# calculator.net
KiCad netlist of a schematic drawn in Altium Designer
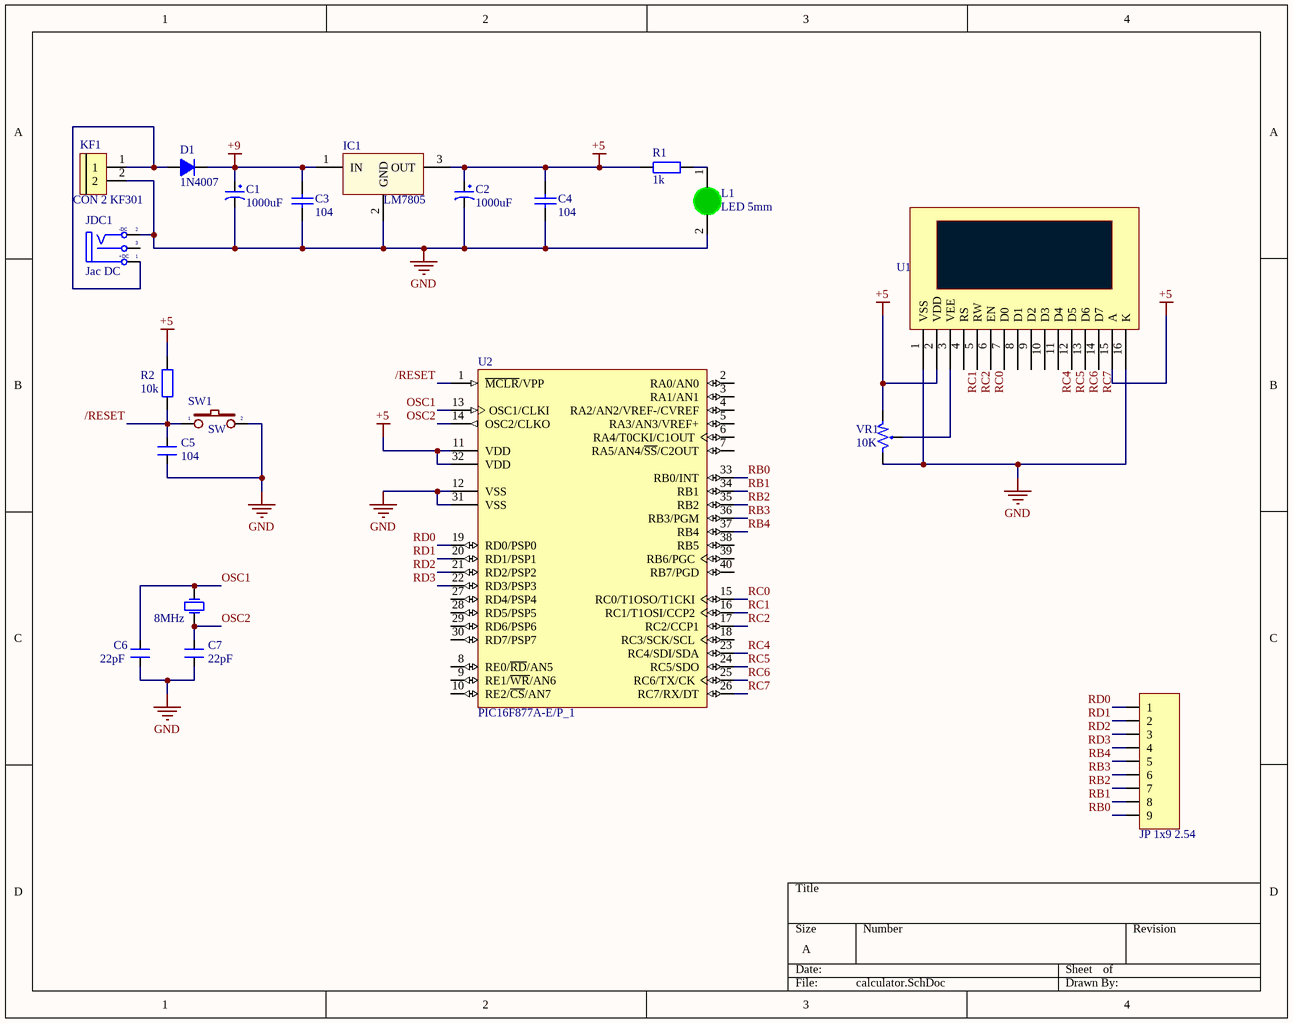
[diagram p0: calculator.SchDoc]

(export (version "E")
  (design (tool "Eeschema 10.0.6"))
  (components
    (comp (ref "C1")
      (value "1000uF")
      (footprint "tu hoa 8mm")
      (description "Cắm")
      (libsource (lib "Capacitor") (part "Tu Hoa 1000uF 16V 8x20"))
    )
    (comp (ref "C2")
      (value "1000uF")
      (footprint "tu hoa 8mm")
      (description "Cắm")
      (libsource (lib "Capacitor") (part "Tu Hoa 1000uF 16V 8x20"))
    )
    (comp (ref "C3")
      (value "104")
      (footprint "tu gom")
      (description "Cắm")
      (libsource (lib "Capacitor") (part "Tu gom 104 50V"))
    )
    (comp (ref "C4")
      (value "104")
      (footprint "tu gom")
      (description "Cắm")
      (libsource (lib "Capacitor") (part "Tu gom 104 50V"))
    )
    (comp (ref "C5")
      (value "104")
      (footprint "CN1.5")
      (description "Cap np 682pF => 104pF")
      (libsource (lib "Cty1") (part "CN1.5"))
    )
    (comp (ref "C6")
      (value "22pF")
      (footprint "CN1.5")
      (description "Cap np 682pF => 104pF")
      (libsource (lib "Cty1") (part "CN1.5"))
    )
    (comp (ref "C7")
      (value "22pF")
      (footprint "CN1.5")
      (description "Cap np 682pF => 104pF")
      (libsource (lib "Cty1") (part "CN1.5"))
    )
    (comp (ref "D1")
      (value "1N4007")
      (footprint "D1A")
      (description "Diode 1A")
      (libsource (lib "Cty1") (part "D1A"))
    )
    (comp (ref "IC1")
      (value "LM7805")
      (footprint "QTO-220")
      (description "On ap +, from + 5 to + 24VDC")
      (libsource (lib "Cty1") (part "LM78xx"))
    )
    (comp (ref "JDC1")
      (value "Jac DC")
      (footprint "DC-IN")
      (description "Jac DC input")
      (libsource (lib "Cty1") (part "DCIN"))
    )
    (comp (ref "JP1")
      (value "JP 1x9 2.54")
      (footprint "JP 1x9 DT")
      (description "Cắm")
      (libsource (lib "Jump") (part "JP 1x9 2.54 Duc Thang"))
    )
    (comp (ref "KF1")
      (value "CON 2 KF301")
      (footprint "Con 2 KF301 5.08")
      (description "Cắm")
      (libsource (lib "Connector") (part "CON 2 KF301"))
    )
    (comp (ref "L1")
      (value "LED 5mm")
      (footprint "LED-5MM-Green")
      (description "Cắm")
      (libsource (lib "Led") (part "LED 5mm Xanh La"))
    )
    (comp (ref "R1")
      (value "1k")
      (footprint "tro vach 1/4w")
      (description "Cắm")
      (libsource (lib "Resistor") (part "Tro Vach 1/4W 5% 1k"))
    )
    (comp (ref "R2")
      (value "10k")
      (footprint "R1/4W")
      (description "Resistor 1/4W")
      (libsource (lib "Cty1") (part "R1/4W"))
    )
    (comp (ref "SW1")
      (value "SW")
      (footprint "SW2")
      (description "Switch button 2 pin")
      (libsource (lib "Cty1") (part "SW2"))
    )
    (comp (ref "U1") (value "LCD") (footprint "LCD16X2") (libsource (lib "Cty1") (part "LCD")))
    (comp (ref "U2")
      (value "PIC16F877A-E/P_1")
      (footprint "PDIP600-P40")
      (fields (field (name "PUBLISHER") "Altium Limited"))
      (libsource (lib "Cty1") (part "PIC16F877A-E/P_1"))
    )
    (comp (ref "VR1")
      (value "10K")
      (footprint "VR1")
      (description "Var Resistor")
      (libsource (lib "syhaunguyen") (part "VR1"))
    )
    (comp (ref "Y1")
      (value "8MHz")
      (footprint "XT2")
      (description "Crystal Oscillator")
      (fields (field (name "PUBLISHER") "Altium Limited"))
      (libsource (lib "Cty1") (part "Crystal"))
    )
  )
  (nets
    (net (code "1") (name "+5") (class "Default")
      (node (ref "C2") (pin "1") (pinfunction "1_1") (pintype "passive"))
      (node (ref "C4") (pin "1") (pinfunction "1_1") (pintype "passive"))
      (node (ref "IC1") (pin "3") (pinfunction "OUT_3") (pintype "passive"))
      (node (ref "R1") (pin "2") (pinfunction "2_2") (pintype "passive"))
      (node (ref "R2") (pin "2") (pinfunction "2_2") (pintype "passive"))
      (node (ref "U1") (pin "15") (pinfunction "A_15") (pintype "passive"))
      (node (ref "U1") (pin "2") (pinfunction "VDD_2") (pintype "passive"))
      (node (ref "U2") (pin "11") (pinfunction "VDD_11") (pintype "power_in"))
      (node (ref "U2") (pin "32") (pinfunction "VDD_32") (pintype "power_in"))
      (node (ref "VR1") (pin "1") (pinfunction "1_1") (pintype "passive"))
    )
    (net (code "2") (name "+9") (class "Default")
      (node (ref "C1") (pin "1") (pinfunction "1_1") (pintype "passive"))
      (node (ref "C3") (pin "1") (pinfunction "1_1") (pintype "passive"))
      (node (ref "D1") (pin "2") (pinfunction "K_2") (pintype "passive"))
      (node (ref "IC1") (pin "1") (pinfunction "IN_1") (pintype "passive"))
    )
    (net (code "3") (name "/OSC1") (class "Default")
      (node (ref "C6") (pin "2") (pinfunction "2_2") (pintype "passive"))
      (node (ref "U2") (pin "13") (pinfunction "OSC1/CLKI_13") (pintype "input"))
      (node (ref "Y1") (pin "1") (pinfunction "OSC1_1") (pintype "passive"))
    )
    (net (code "4") (name "/OSC2") (class "Default")
      (node (ref "C7") (pin "2") (pinfunction "2_2") (pintype "passive"))
      (node (ref "U2") (pin "14") (pinfunction "OSC2/CLKO_14") (pintype "output"))
      (node (ref "Y1") (pin "2") (pinfunction "OSC2_2") (pintype "passive"))
    )
    (net (code "5") (name "/RB0") (class "Default")
      (node (ref "JP1") (pin "9") (pinfunction "9_9") (pintype "passive"))
      (node (ref "U2") (pin "33") (pinfunction "RB0/INT_33") (pintype "bidirectional"))
    )
    (net (code "6") (name "/RB1") (class "Default")
      (node (ref "JP1") (pin "8") (pinfunction "8_8") (pintype "passive"))
      (node (ref "U2") (pin "34") (pinfunction "RB1_34") (pintype "bidirectional"))
    )
    (net (code "7") (name "/RB2") (class "Default")
      (node (ref "JP1") (pin "7") (pinfunction "7_7") (pintype "passive"))
      (node (ref "U2") (pin "35") (pinfunction "RB2_35") (pintype "bidirectional"))
    )
    (net (code "8") (name "/RB3") (class "Default")
      (node (ref "JP1") (pin "6") (pinfunction "6_6") (pintype "passive"))
      (node (ref "U2") (pin "36") (pinfunction "RB3/PGM_36") (pintype "bidirectional"))
    )
    (net (code "9") (name "/RB4") (class "Default")
      (node (ref "JP1") (pin "5") (pinfunction "5_5") (pintype "passive"))
      (node (ref "U2") (pin "37") (pinfunction "RB4_37") (pintype "bidirectional"))
    )
    (net (code "10") (name "/RC0") (class "Default")
      (node (ref "U1") (pin "6") (pinfunction "EN_6") (pintype "passive"))
      (node (ref "U2") (pin "15") (pinfunction "RC0/T1OSO/T1CKI_15") (pintype "bidirectional"))
    )
    (net (code "11") (name "/RC1") (class "Default")
      (node (ref "U1") (pin "4") (pinfunction "RS_4") (pintype "passive"))
      (node (ref "U2") (pin "16") (pinfunction "RC1/T1OSI/CCP2_16") (pintype "bidirectional"))
    )
    (net (code "12") (name "/RC2") (class "Default")
      (node (ref "U1") (pin "5") (pinfunction "RW_5") (pintype "passive"))
      (node (ref "U2") (pin "17") (pinfunction "RC2/CCP1_17") (pintype "bidirectional"))
    )
    (net (code "13") (name "/RC4") (class "Default")
      (node (ref "U1") (pin "11") (pinfunction "D4_11") (pintype "passive"))
      (node (ref "U2") (pin "23") (pinfunction "RC4/SDI/SDA_23") (pintype "bidirectional"))
    )
    (net (code "14") (name "/RC5") (class "Default")
      (node (ref "U1") (pin "12") (pinfunction "D5_12") (pintype "passive"))
      (node (ref "U2") (pin "24") (pinfunction "RC5/SDO_24") (pintype "bidirectional"))
    )
    (net (code "15") (name "/RC6") (class "Default")
      (node (ref "U1") (pin "13") (pinfunction "D6_13") (pintype "passive"))
      (node (ref "U2") (pin "25") (pinfunction "RC6/TX/CK_25") (pintype "bidirectional"))
    )
    (net (code "16") (name "/RC7") (class "Default")
      (node (ref "U1") (pin "14") (pinfunction "D7_14") (pintype "passive"))
      (node (ref "U2") (pin "26") (pinfunction "RC7/RX/DT_26") (pintype "bidirectional"))
    )
    (net (code "17") (name "/RD0") (class "Default")
      (node (ref "JP1") (pin "1") (pinfunction "1_1") (pintype "passive"))
      (node (ref "U2") (pin "19") (pinfunction "RD0/PSP0_19") (pintype "bidirectional"))
    )
    (net (code "18") (name "/RD1") (class "Default")
      (node (ref "JP1") (pin "2") (pinfunction "2_2") (pintype "passive"))
      (node (ref "U2") (pin "20") (pinfunction "RD1/PSP1_20") (pintype "bidirectional"))
    )
    (net (code "19") (name "/RD2") (class "Default")
      (node (ref "JP1") (pin "3") (pinfunction "3_3") (pintype "passive"))
      (node (ref "U2") (pin "21") (pinfunction "RD2/PSP2_21") (pintype "bidirectional"))
    )
    (net (code "20") (name "/RD3") (class "Default")
      (node (ref "JP1") (pin "4") (pinfunction "4_4") (pintype "passive"))
      (node (ref "U2") (pin "22") (pinfunction "RD3/PSP3_22") (pintype "bidirectional"))
    )
    (net (code "21") (name "/{slash}RESET") (class "Default")
      (node (ref "C5") (pin "2") (pinfunction "2_2") (pintype "passive"))
      (node (ref "R2") (pin "1") (pinfunction "1_1") (pintype "passive"))
      (node (ref "SW1") (pin "1") (pinfunction "1_1") (pintype "passive"))
      (node (ref "U2") (pin "1") (pinfunction "~{MCLR}/VPP_1") (pintype "input"))
    )
    (net (code "22") (name "GND") (class "Default")
      (node (ref "C1") (pin "2") (pinfunction "2_2") (pintype "passive"))
      (node (ref "C2") (pin "2") (pinfunction "2_2") (pintype "passive"))
      (node (ref "C3") (pin "2") (pinfunction "2_2") (pintype "passive"))
      (node (ref "C4") (pin "2") (pinfunction "2_2") (pintype "passive"))
      (node (ref "C5") (pin "1") (pinfunction "1_1") (pintype "passive"))
      (node (ref "C6") (pin "1") (pinfunction "1_1") (pintype "passive"))
      (node (ref "C7") (pin "1") (pinfunction "1_1") (pintype "passive"))
      (node (ref "IC1") (pin "2") (pinfunction "GND_2") (pintype "passive"))
      (node (ref "JDC1") (pin "2") (pinfunction "TN_2") (pintype "passive"))
      (node (ref "KF1") (pin "2") (pinfunction "2_2") (pintype "passive"))
      (node (ref "L1") (pin "2") (pinfunction "K_2") (pintype "passive"))
      (node (ref "SW1") (pin "2") (pinfunction "2_2") (pintype "passive"))
      (node (ref "U1") (pin "1") (pinfunction "VSS_1") (pintype "passive"))
      (node (ref "U1") (pin "16") (pinfunction "K_16") (pintype "passive"))
      (node (ref "U2") (pin "12") (pinfunction "VSS_12") (pintype "power_in"))
      (node (ref "U2") (pin "31") (pinfunction "VSS_31") (pintype "power_in"))
      (node (ref "VR1") (pin "3") (pinfunction "3_3") (pintype "passive"))
    )
    (net (code "23") (name "Net-(D1-A)") (class "Default")
      (node (ref "D1") (pin "1") (pinfunction "A_1") (pintype "passive"))
      (node (ref "JDC1") (pin "1") (pinfunction "T_1") (pintype "passive"))
      (node (ref "KF1") (pin "1") (pinfunction "1_1") (pintype "passive"))
    )
    (net (code "24") (name "Net-(L1-A)") (class "Default")
      (node (ref "L1") (pin "1") (pinfunction "A_1") (pintype "passive"))
      (node (ref "R1") (pin "1") (pinfunction "1_1") (pintype "passive"))
    )
    (net (code "25") (name "Net-(U1-VEE)") (class "Default")
      (node (ref "U1") (pin "3") (pinfunction "VEE_3") (pintype "passive"))
      (node (ref "VR1") (pin "2") (pinfunction "2_2") (pintype "passive"))
    )
    (net (code "26") (name "unconnected-(JDC1-S-Pad3)") (class "Default")
      (node (ref "JDC1") (pin "3") (pinfunction "S_3") (pintype "power_in"))
    )
    (net (code "27") (name "unconnected-(U1-D0-Pad7)") (class "Default")
      (node (ref "U1") (pin "7") (pinfunction "D0_7") (pintype "passive"))
    )
    (net (code "28") (name "unconnected-(U1-D1-Pad8)") (class "Default")
      (node (ref "U1") (pin "8") (pinfunction "D1_8") (pintype "passive"))
    )
    (net (code "29") (name "unconnected-(U1-D2-Pad9)") (class "Default")
      (node (ref "U1") (pin "9") (pinfunction "D2_9") (pintype "passive"))
    )
    (net (code "30") (name "unconnected-(U1-D3-Pad10)") (class "Default")
      (node (ref "U1") (pin "10") (pinfunction "D3_10") (pintype "passive"))
    )
    (net (code "31") (name "unconnected-(U2-RA0{slash}AN0-Pad2)") (class "Default")
      (node (ref "U2") (pin "2") (pinfunction "RA0/AN0_2") (pintype "bidirectional"))
    )
    (net (code "32") (name "unconnected-(U2-RA1{slash}AN1-Pad3)") (class "Default")
      (node (ref "U2") (pin "3") (pinfunction "RA1/AN1_3") (pintype "bidirectional"))
    )
    (net (code "33") (name "unconnected-(U2-RA2{slash}AN2{slash}VREF-{slash}CVREF-Pad4)") (class "Default")
      (node (ref "U2") (pin "4") (pinfunction "RA2/AN2/VREF-/CVREF_4") (pintype "bidirectional"))
    )
    (net (code "34") (name "unconnected-(U2-RA3{slash}AN3{slash}VREF+-Pad5)") (class "Default")
      (node (ref "U2") (pin "5") (pinfunction "RA3/AN3/VREF+_5") (pintype "bidirectional"))
    )
    (net (code "35") (name "unconnected-(U2-RA4{slash}T0CKI{slash}C1OUT-Pad6)") (class "Default")
      (node (ref "U2") (pin "6") (pinfunction "RA4/T0CKI/C1OUT_6") (pintype "bidirectional"))
    )
    (net (code "36") (name "unconnected-(U2-RA5{slash}AN4{slash}~{SS}{slash}C2OUT-Pad7)") (class "Default")
      (node (ref "U2") (pin "7") (pinfunction "RA5/AN4/~{SS}/C2OUT_7") (pintype "bidirectional"))
    )
    (net (code "37") (name "unconnected-(U2-RB5-Pad38)") (class "Default")
      (node (ref "U2") (pin "38") (pinfunction "RB5_38") (pintype "bidirectional"))
    )
    (net (code "38") (name "unconnected-(U2-RB6{slash}PGC-Pad39)") (class "Default")
      (node (ref "U2") (pin "39") (pinfunction "RB6/PGC_39") (pintype "bidirectional"))
    )
    (net (code "39") (name "unconnected-(U2-RB7{slash}PGD-Pad40)") (class "Default")
      (node (ref "U2") (pin "40") (pinfunction "RB7/PGD_40") (pintype "bidirectional"))
    )
    (net (code "40") (name "unconnected-(U2-RC3{slash}SCK{slash}SCL-Pad18)") (class "Default")
      (node (ref "U2") (pin "18") (pinfunction "RC3/SCK/SCL_18") (pintype "bidirectional"))
    )
    (net (code "41") (name "unconnected-(U2-RD4{slash}PSP4-Pad27)") (class "Default")
      (node (ref "U2") (pin "27") (pinfunction "RD4/PSP4_27") (pintype "bidirectional"))
    )
    (net (code "42") (name "unconnected-(U2-RD5{slash}PSP5-Pad28)") (class "Default")
      (node (ref "U2") (pin "28") (pinfunction "RD5/PSP5_28") (pintype "bidirectional"))
    )
    (net (code "43") (name "unconnected-(U2-RD6{slash}PSP6-Pad29)") (class "Default")
      (node (ref "U2") (pin "29") (pinfunction "RD6/PSP6_29") (pintype "bidirectional"))
    )
    (net (code "44") (name "unconnected-(U2-RD7{slash}PSP7-Pad30)") (class "Default")
      (node (ref "U2") (pin "30") (pinfunction "RD7/PSP7_30") (pintype "bidirectional"))
    )
    (net (code "45") (name "unconnected-(U2-RE0{slash}~{RD}{slash}AN5-Pad8)") (class "Default")
      (node (ref "U2") (pin "8") (pinfunction "RE0/~{RD}/AN5_8") (pintype "bidirectional"))
    )
    (net (code "46") (name "unconnected-(U2-RE1{slash}~{WR}{slash}AN6-Pad9)") (class "Default")
      (node (ref "U2") (pin "9") (pinfunction "RE1/~{WR}/AN6_9") (pintype "bidirectional"))
    )
    (net (code "47") (name "unconnected-(U2-RE2{slash}~{CS}{slash}AN7-Pad10)") (class "Default")
      (node (ref "U2") (pin "10") (pinfunction "RE2/~{CS}/AN7_10") (pintype "bidirectional"))
    )
  )
)
